# z80_test.net
KiCad netlist of a schematic drawn in EAGLE
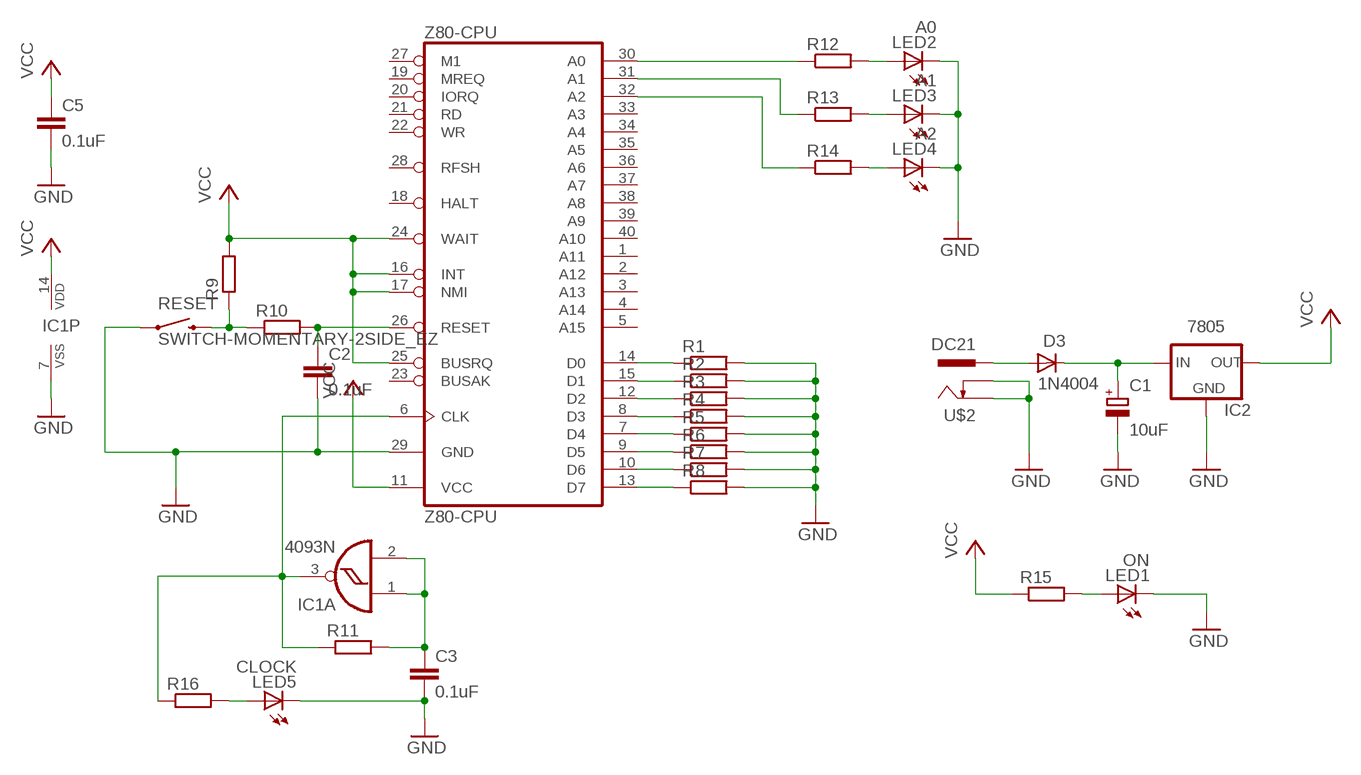
[diagram p0: schematic, sheet 1]

(export (version "E")
  (design (tool "Eeschema 10.0.6"))
  (components
    (comp (ref "C1")
      (value "10uF")
      (footprint "eagle-import:E2,5-6E")
      (libsource (lib "eagle-import") (part "CPOL-EUE2,5-6E"))
    )
    (comp (ref "C2")
      (value "0.1uF")
      (footprint "eagle-import:C025-025X050")
      (libsource (lib "eagle-import") (part "C-EU025-025X050"))
    )
    (comp (ref "C3")
      (value "0.1uF")
      (footprint "eagle-import:C025-025X050")
      (libsource (lib "eagle-import") (part "C-EU025-025X050"))
    )
    (comp (ref "C5")
      (value "0.1uF")
      (footprint "eagle-import:C025-025X050")
      (libsource (lib "eagle-import") (part "C-EU025-025X050"))
    )
    (comp (ref "D3")
      (value "1N4004")
      (footprint "eagle-import:DO41-10")
      (libsource (lib "eagle-import") (part "1N4004"))
    )
    (comp (ref "IC1")
      (value "4093N")
      (footprint "eagle-import:DIL14")
      (libsource (lib "eagle-import") (part "4093N"))
    )
    (comp (ref "IC2")
      (value "7805")
      (footprint "eagle-import:78XXL")
      (libsource (lib "eagle-import") (part "78XXL"))
    )
    (comp (ref "LED1")
      (value "ON")
      (footprint "eagle-import:LED3MM")
      (libsource (lib "eagle-import") (part "LED3MM"))
    )
    (comp (ref "LED2")
      (value "A0")
      (footprint "eagle-import:LED3MM")
      (libsource (lib "eagle-import") (part "LED3MM"))
    )
    (comp (ref "LED3")
      (value "A1")
      (footprint "eagle-import:LED3MM")
      (libsource (lib "eagle-import") (part "LED3MM"))
    )
    (comp (ref "LED4")
      (value "A2")
      (footprint "eagle-import:LED3MM")
      (libsource (lib "eagle-import") (part "LED3MM"))
    )
    (comp (ref "LED5")
      (value "CLOCK")
      (footprint "eagle-import:LED3MM")
      (libsource (lib "eagle-import") (part "LED3MM"))
    )
    (comp (ref "R1")
      (value "10K")
      (footprint "eagle-import:0204_7")
      (libsource (lib "eagle-import") (part "R-EU_0204/7"))
    )
    (comp (ref "R2")
      (value "10K")
      (footprint "eagle-import:0204_7")
      (libsource (lib "eagle-import") (part "R-EU_0204/7"))
    )
    (comp (ref "R3")
      (value "10K")
      (footprint "eagle-import:0204_7")
      (libsource (lib "eagle-import") (part "R-EU_0204/7"))
    )
    (comp (ref "R4")
      (value "10K")
      (footprint "eagle-import:0204_7")
      (libsource (lib "eagle-import") (part "R-EU_0204/7"))
    )
    (comp (ref "R5")
      (value "10K")
      (footprint "eagle-import:0204_7")
      (libsource (lib "eagle-import") (part "R-EU_0204/7"))
    )
    (comp (ref "R6")
      (value "10K")
      (footprint "eagle-import:0204_7")
      (libsource (lib "eagle-import") (part "R-EU_0204/7"))
    )
    (comp (ref "R7")
      (value "10K")
      (footprint "eagle-import:0204_7")
      (libsource (lib "eagle-import") (part "R-EU_0204/7"))
    )
    (comp (ref "R8")
      (value "10K")
      (footprint "eagle-import:0204_7")
      (libsource (lib "eagle-import") (part "R-EU_0204/7"))
    )
    (comp (ref "R9")
      (value "10K")
      (footprint "eagle-import:0204_7")
      (libsource (lib "eagle-import") (part "R-EU_0204/7"))
    )
    (comp (ref "R10")
      (value "330")
      (footprint "eagle-import:0204_7")
      (libsource (lib "eagle-import") (part "R-EU_0204/7"))
    )
    (comp (ref "R11")
      (value "68K")
      (footprint "eagle-import:0204_7")
      (libsource (lib "eagle-import") (part "R-EU_0204/7"))
    )
    (comp (ref "R12")
      (value "470")
      (footprint "eagle-import:0204_7")
      (libsource (lib "eagle-import") (part "R-EU_0204/7"))
    )
    (comp (ref "R13")
      (value "470")
      (footprint "eagle-import:0204_7")
      (libsource (lib "eagle-import") (part "R-EU_0204/7"))
    )
    (comp (ref "R14")
      (value "470")
      (footprint "eagle-import:0204_7")
      (libsource (lib "eagle-import") (part "R-EU_0204/7"))
    )
    (comp (ref "R15")
      (value "470")
      (footprint "eagle-import:0204_7")
      (libsource (lib "eagle-import") (part "R-EU_0204/7"))
    )
    (comp (ref "R16")
      (value "470")
      (footprint "eagle-import:0204_7")
      (libsource (lib "eagle-import") (part "R-EU_0204/7"))
    )
    (comp (ref "RESET")
      (value "SWITCH-MOMENTARY-2SIDE_EZ")
      (footprint "eagle-import:TACTILE-PTH-SIDEEZ")
      (libsource (lib "eagle-import") (part "SWITCH-MOMENTARY-2SIDE_EZ"))
    )
    (comp (ref "U$2")
      (value "DC21")
      (footprint "eagle-import:DCSKT")
      (libsource (lib "eagle-import") (part "DC21"))
    )
    (comp (ref "Z80-CPU")
      (value "Z80-CPU")
      (footprint "eagle-import:DIL40")
      (libsource (lib "eagle-import") (part "Z80CPU"))
    )
  )
  (nets
    (net (code "1") (name "GND") (class "Default")
      (node (ref "C1") (pin "-") (pinfunction "-_-") (pintype "passive"))
      (node (ref "C2") (pin "2") (pinfunction "2_2") (pintype "passive"))
      (node (ref "C3") (pin "2") (pinfunction "2_2") (pintype "passive"))
      (node (ref "C5") (pin "2") (pinfunction "2_2") (pintype "passive"))
      (node (ref "IC1") (pin "7") (pinfunction "VSS_7") (pintype "power_in"))
      (node (ref "IC2") (pin "GND") (pinfunction "GND_GND") (pintype "input"))
      (node (ref "LED1") (pin "K") (pinfunction "C_K") (pintype "passive"))
      (node (ref "LED2") (pin "K") (pinfunction "C_K") (pintype "passive"))
      (node (ref "LED3") (pin "K") (pinfunction "C_K") (pintype "passive"))
      (node (ref "LED4") (pin "K") (pinfunction "C_K") (pintype "passive"))
      (node (ref "LED5") (pin "K") (pinfunction "C_K") (pintype "passive"))
      (node (ref "R1") (pin "2") (pinfunction "2_2") (pintype "passive"))
      (node (ref "R2") (pin "2") (pinfunction "2_2") (pintype "passive"))
      (node (ref "R3") (pin "2") (pinfunction "2_2") (pintype "passive"))
      (node (ref "R4") (pin "2") (pinfunction "2_2") (pintype "passive"))
      (node (ref "R5") (pin "2") (pinfunction "2_2") (pintype "passive"))
      (node (ref "R6") (pin "2") (pinfunction "2_2") (pintype "passive"))
      (node (ref "R7") (pin "2") (pinfunction "2_2") (pintype "passive"))
      (node (ref "R8") (pin "2") (pinfunction "2_2") (pintype "passive"))
      (node (ref "RESET") (pin "1") (pinfunction "1_1") (pintype "passive"))
      (node (ref "U$2") (pin "2") (pinfunction "2_2") (pintype "passive"))
      (node (ref "U$2") (pin "3") (pinfunction "3_3") (pintype "passive"))
      (node (ref "Z80-CPU") (pin "29") (pinfunction "GND_29") (pintype "power_in"))
    )
    (net (code "2") (name "Net-(C1-Pad+)") (class "Default")
      (node (ref "C1") (pin "+") (pinfunction "+_+") (pintype "passive"))
      (node (ref "D3") (pin "C") (pinfunction "C_C") (pintype "passive"))
      (node (ref "IC2") (pin "IN") (pinfunction "IN_IN") (pintype "input"))
    )
    (net (code "3") (name "Net-(D3-PadA)") (class "Default")
      (node (ref "D3") (pin "A") (pinfunction "A_A") (pintype "passive"))
      (node (ref "U$2") (pin "1") (pinfunction "1_1") (pintype "passive"))
    )
    (net (code "4") (name "Net-(IC1A-I0)") (class "Default")
      (node (ref "C3") (pin "1") (pinfunction "1_1") (pintype "passive"))
      (node (ref "IC1") (pin "1") (pinfunction "I0_1") (pintype "input"))
      (node (ref "IC1") (pin "2") (pinfunction "I1_2") (pintype "input"))
      (node (ref "R11") (pin "2") (pinfunction "2_2") (pintype "passive"))
    )
    (net (code "5") (name "Net-(IC1A-O)") (class "Default")
      (node (ref "IC1") (pin "3") (pinfunction "O_3") (pintype "output"))
      (node (ref "R11") (pin "1") (pinfunction "1_1") (pintype "passive"))
      (node (ref "R16") (pin "1") (pinfunction "1_1") (pintype "passive"))
      (node (ref "Z80-CPU") (pin "6") (pinfunction "CLK_6") (pintype "input"))
    )
    (net (code "6") (name "Net-(LED1-PadA)") (class "Default")
      (node (ref "LED1") (pin "A") (pinfunction "A_A") (pintype "passive"))
      (node (ref "R15") (pin "2") (pinfunction "2_2") (pintype "passive"))
    )
    (net (code "7") (name "Net-(LED2-PadA)") (class "Default")
      (node (ref "LED2") (pin "A") (pinfunction "A_A") (pintype "passive"))
      (node (ref "R12") (pin "2") (pinfunction "2_2") (pintype "passive"))
    )
    (net (code "8") (name "Net-(LED3-PadA)") (class "Default")
      (node (ref "LED3") (pin "A") (pinfunction "A_A") (pintype "passive"))
      (node (ref "R13") (pin "2") (pinfunction "2_2") (pintype "passive"))
    )
    (net (code "9") (name "Net-(LED4-PadA)") (class "Default")
      (node (ref "LED4") (pin "A") (pinfunction "A_A") (pintype "passive"))
      (node (ref "R14") (pin "2") (pinfunction "2_2") (pintype "passive"))
    )
    (net (code "10") (name "Net-(LED5-PadA)") (class "Default")
      (node (ref "LED5") (pin "A") (pinfunction "A_A") (pintype "passive"))
      (node (ref "R16") (pin "2") (pinfunction "2_2") (pintype "passive"))
    )
    (net (code "11") (name "Net-(R10-Pad1)") (class "Default")
      (node (ref "R10") (pin "1") (pinfunction "1_1") (pintype "passive"))
      (node (ref "R9") (pin "1") (pinfunction "1_1") (pintype "passive"))
      (node (ref "RESET") (pin "2") (pinfunction "2_2") (pintype "passive"))
    )
    (net (code "12") (name "Net-(Z80-CPU-A0)") (class "Default")
      (node (ref "R12") (pin "1") (pinfunction "1_1") (pintype "passive"))
      (node (ref "Z80-CPU") (pin "30") (pinfunction "A0_30") (pintype "output"))
    )
    (net (code "13") (name "Net-(Z80-CPU-A1)") (class "Default")
      (node (ref "R13") (pin "1") (pinfunction "1_1") (pintype "passive"))
      (node (ref "Z80-CPU") (pin "31") (pinfunction "A1_31") (pintype "output"))
    )
    (net (code "14") (name "Net-(Z80-CPU-A2)") (class "Default")
      (node (ref "R14") (pin "1") (pinfunction "1_1") (pintype "passive"))
      (node (ref "Z80-CPU") (pin "32") (pinfunction "A2_32") (pintype "output"))
    )
    (net (code "15") (name "Net-(Z80-CPU-D0)") (class "Default")
      (node (ref "R1") (pin "1") (pinfunction "1_1") (pintype "passive"))
      (node (ref "Z80-CPU") (pin "14") (pinfunction "D0_14") (pintype "bidirectional"))
    )
    (net (code "16") (name "Net-(Z80-CPU-D1)") (class "Default")
      (node (ref "R2") (pin "1") (pinfunction "1_1") (pintype "passive"))
      (node (ref "Z80-CPU") (pin "15") (pinfunction "D1_15") (pintype "bidirectional"))
    )
    (net (code "17") (name "Net-(Z80-CPU-D2)") (class "Default")
      (node (ref "R3") (pin "1") (pinfunction "1_1") (pintype "passive"))
      (node (ref "Z80-CPU") (pin "12") (pinfunction "D2_12") (pintype "bidirectional"))
    )
    (net (code "18") (name "Net-(Z80-CPU-D3)") (class "Default")
      (node (ref "R4") (pin "1") (pinfunction "1_1") (pintype "passive"))
      (node (ref "Z80-CPU") (pin "8") (pinfunction "D3_8") (pintype "bidirectional"))
    )
    (net (code "19") (name "Net-(Z80-CPU-D4)") (class "Default")
      (node (ref "R5") (pin "1") (pinfunction "1_1") (pintype "passive"))
      (node (ref "Z80-CPU") (pin "7") (pinfunction "D4_7") (pintype "bidirectional"))
    )
    (net (code "20") (name "Net-(Z80-CPU-D5)") (class "Default")
      (node (ref "R6") (pin "1") (pinfunction "1_1") (pintype "passive"))
      (node (ref "Z80-CPU") (pin "9") (pinfunction "D5_9") (pintype "bidirectional"))
    )
    (net (code "21") (name "Net-(Z80-CPU-D6)") (class "Default")
      (node (ref "R7") (pin "1") (pinfunction "1_1") (pintype "passive"))
      (node (ref "Z80-CPU") (pin "10") (pinfunction "D6_10") (pintype "bidirectional"))
    )
    (net (code "22") (name "Net-(Z80-CPU-D7)") (class "Default")
      (node (ref "R8") (pin "1") (pinfunction "1_1") (pintype "passive"))
      (node (ref "Z80-CPU") (pin "13") (pinfunction "D7_13") (pintype "bidirectional"))
    )
    (net (code "23") (name "Net-(Z80-CPU-RESET)") (class "Default")
      (node (ref "C2") (pin "1") (pinfunction "1_1") (pintype "passive"))
      (node (ref "R10") (pin "2") (pinfunction "2_2") (pintype "passive"))
      (node (ref "Z80-CPU") (pin "26") (pinfunction "RESET_26") (pintype "input"))
    )
    (net (code "24") (name "VCC") (class "Default")
      (node (ref "C5") (pin "1") (pinfunction "1_1") (pintype "passive"))
      (node (ref "IC1") (pin "14") (pinfunction "VDD_14") (pintype "power_in"))
      (node (ref "IC2") (pin "OUT") (pinfunction "OUT_OUT") (pintype "passive"))
      (node (ref "R15") (pin "1") (pinfunction "1_1") (pintype "passive"))
      (node (ref "R9") (pin "2") (pinfunction "2_2") (pintype "passive"))
      (node (ref "Z80-CPU") (pin "11") (pinfunction "VCC_11") (pintype "power_in"))
      (node (ref "Z80-CPU") (pin "16") (pinfunction "INT_16") (pintype "input"))
      (node (ref "Z80-CPU") (pin "17") (pinfunction "NMI_17") (pintype "input"))
      (node (ref "Z80-CPU") (pin "24") (pinfunction "WAIT_24") (pintype "input"))
      (node (ref "Z80-CPU") (pin "25") (pinfunction "BUSRQ_25") (pintype "input"))
    )
    (net (code "25") (name "unconnected-(Z80-CPU-A3-Pad33)") (class "Default")
      (node (ref "Z80-CPU") (pin "33") (pinfunction "A3_33") (pintype "output"))
    )
    (net (code "26") (name "unconnected-(Z80-CPU-A4-Pad34)") (class "Default")
      (node (ref "Z80-CPU") (pin "34") (pinfunction "A4_34") (pintype "output"))
    )
    (net (code "27") (name "unconnected-(Z80-CPU-A5-Pad35)") (class "Default")
      (node (ref "Z80-CPU") (pin "35") (pinfunction "A5_35") (pintype "output"))
    )
    (net (code "28") (name "unconnected-(Z80-CPU-A6-Pad36)") (class "Default")
      (node (ref "Z80-CPU") (pin "36") (pinfunction "A6_36") (pintype "output"))
    )
    (net (code "29") (name "unconnected-(Z80-CPU-A7-Pad37)") (class "Default")
      (node (ref "Z80-CPU") (pin "37") (pinfunction "A7_37") (pintype "output"))
    )
    (net (code "30") (name "unconnected-(Z80-CPU-A8-Pad38)") (class "Default")
      (node (ref "Z80-CPU") (pin "38") (pinfunction "A8_38") (pintype "output"))
    )
    (net (code "31") (name "unconnected-(Z80-CPU-A9-Pad39)") (class "Default")
      (node (ref "Z80-CPU") (pin "39") (pinfunction "A9_39") (pintype "output"))
    )
    (net (code "32") (name "unconnected-(Z80-CPU-A10-Pad40)") (class "Default")
      (node (ref "Z80-CPU") (pin "40") (pinfunction "A10_40") (pintype "output"))
    )
    (net (code "33") (name "unconnected-(Z80-CPU-A11-Pad1)") (class "Default")
      (node (ref "Z80-CPU") (pin "1") (pinfunction "A11_1") (pintype "output"))
    )
    (net (code "34") (name "unconnected-(Z80-CPU-A12-Pad2)") (class "Default")
      (node (ref "Z80-CPU") (pin "2") (pinfunction "A12_2") (pintype "output"))
    )
    (net (code "35") (name "unconnected-(Z80-CPU-A13-Pad3)") (class "Default")
      (node (ref "Z80-CPU") (pin "3") (pinfunction "A13_3") (pintype "output"))
    )
    (net (code "36") (name "unconnected-(Z80-CPU-A14-Pad4)") (class "Default")
      (node (ref "Z80-CPU") (pin "4") (pinfunction "A14_4") (pintype "output"))
    )
    (net (code "37") (name "unconnected-(Z80-CPU-A15-Pad5)") (class "Default")
      (node (ref "Z80-CPU") (pin "5") (pinfunction "A15_5") (pintype "output"))
    )
    (net (code "38") (name "unconnected-(Z80-CPU-BUSAK-Pad23)") (class "Default")
      (node (ref "Z80-CPU") (pin "23") (pinfunction "BUSAK_23") (pintype "output"))
    )
    (net (code "39") (name "unconnected-(Z80-CPU-HALT-Pad18)") (class "Default")
      (node (ref "Z80-CPU") (pin "18") (pinfunction "HALT_18") (pintype "output"))
    )
    (net (code "40") (name "unconnected-(Z80-CPU-IORQ-Pad20)") (class "Default")
      (node (ref "Z80-CPU") (pin "20") (pinfunction "IORQ_20") (pintype "output"))
    )
    (net (code "41") (name "unconnected-(Z80-CPU-M1-Pad27)") (class "Default")
      (node (ref "Z80-CPU") (pin "27") (pinfunction "M1_27") (pintype "output"))
    )
    (net (code "42") (name "unconnected-(Z80-CPU-MREQ-Pad19)") (class "Default")
      (node (ref "Z80-CPU") (pin "19") (pinfunction "MREQ_19") (pintype "output"))
    )
    (net (code "43") (name "unconnected-(Z80-CPU-RD-Pad21)") (class "Default")
      (node (ref "Z80-CPU") (pin "21") (pinfunction "RD_21") (pintype "output"))
    )
    (net (code "44") (name "unconnected-(Z80-CPU-RFSH-Pad28)") (class "Default")
      (node (ref "Z80-CPU") (pin "28") (pinfunction "RFSH_28") (pintype "output"))
    )
    (net (code "45") (name "unconnected-(Z80-CPU-WR-Pad22)") (class "Default")
      (node (ref "Z80-CPU") (pin "22") (pinfunction "WR_22") (pintype "output"))
    )
  )
)
